# Controller_Sheet.net
KiCad netlist of a schematic drawn in Altium Designer
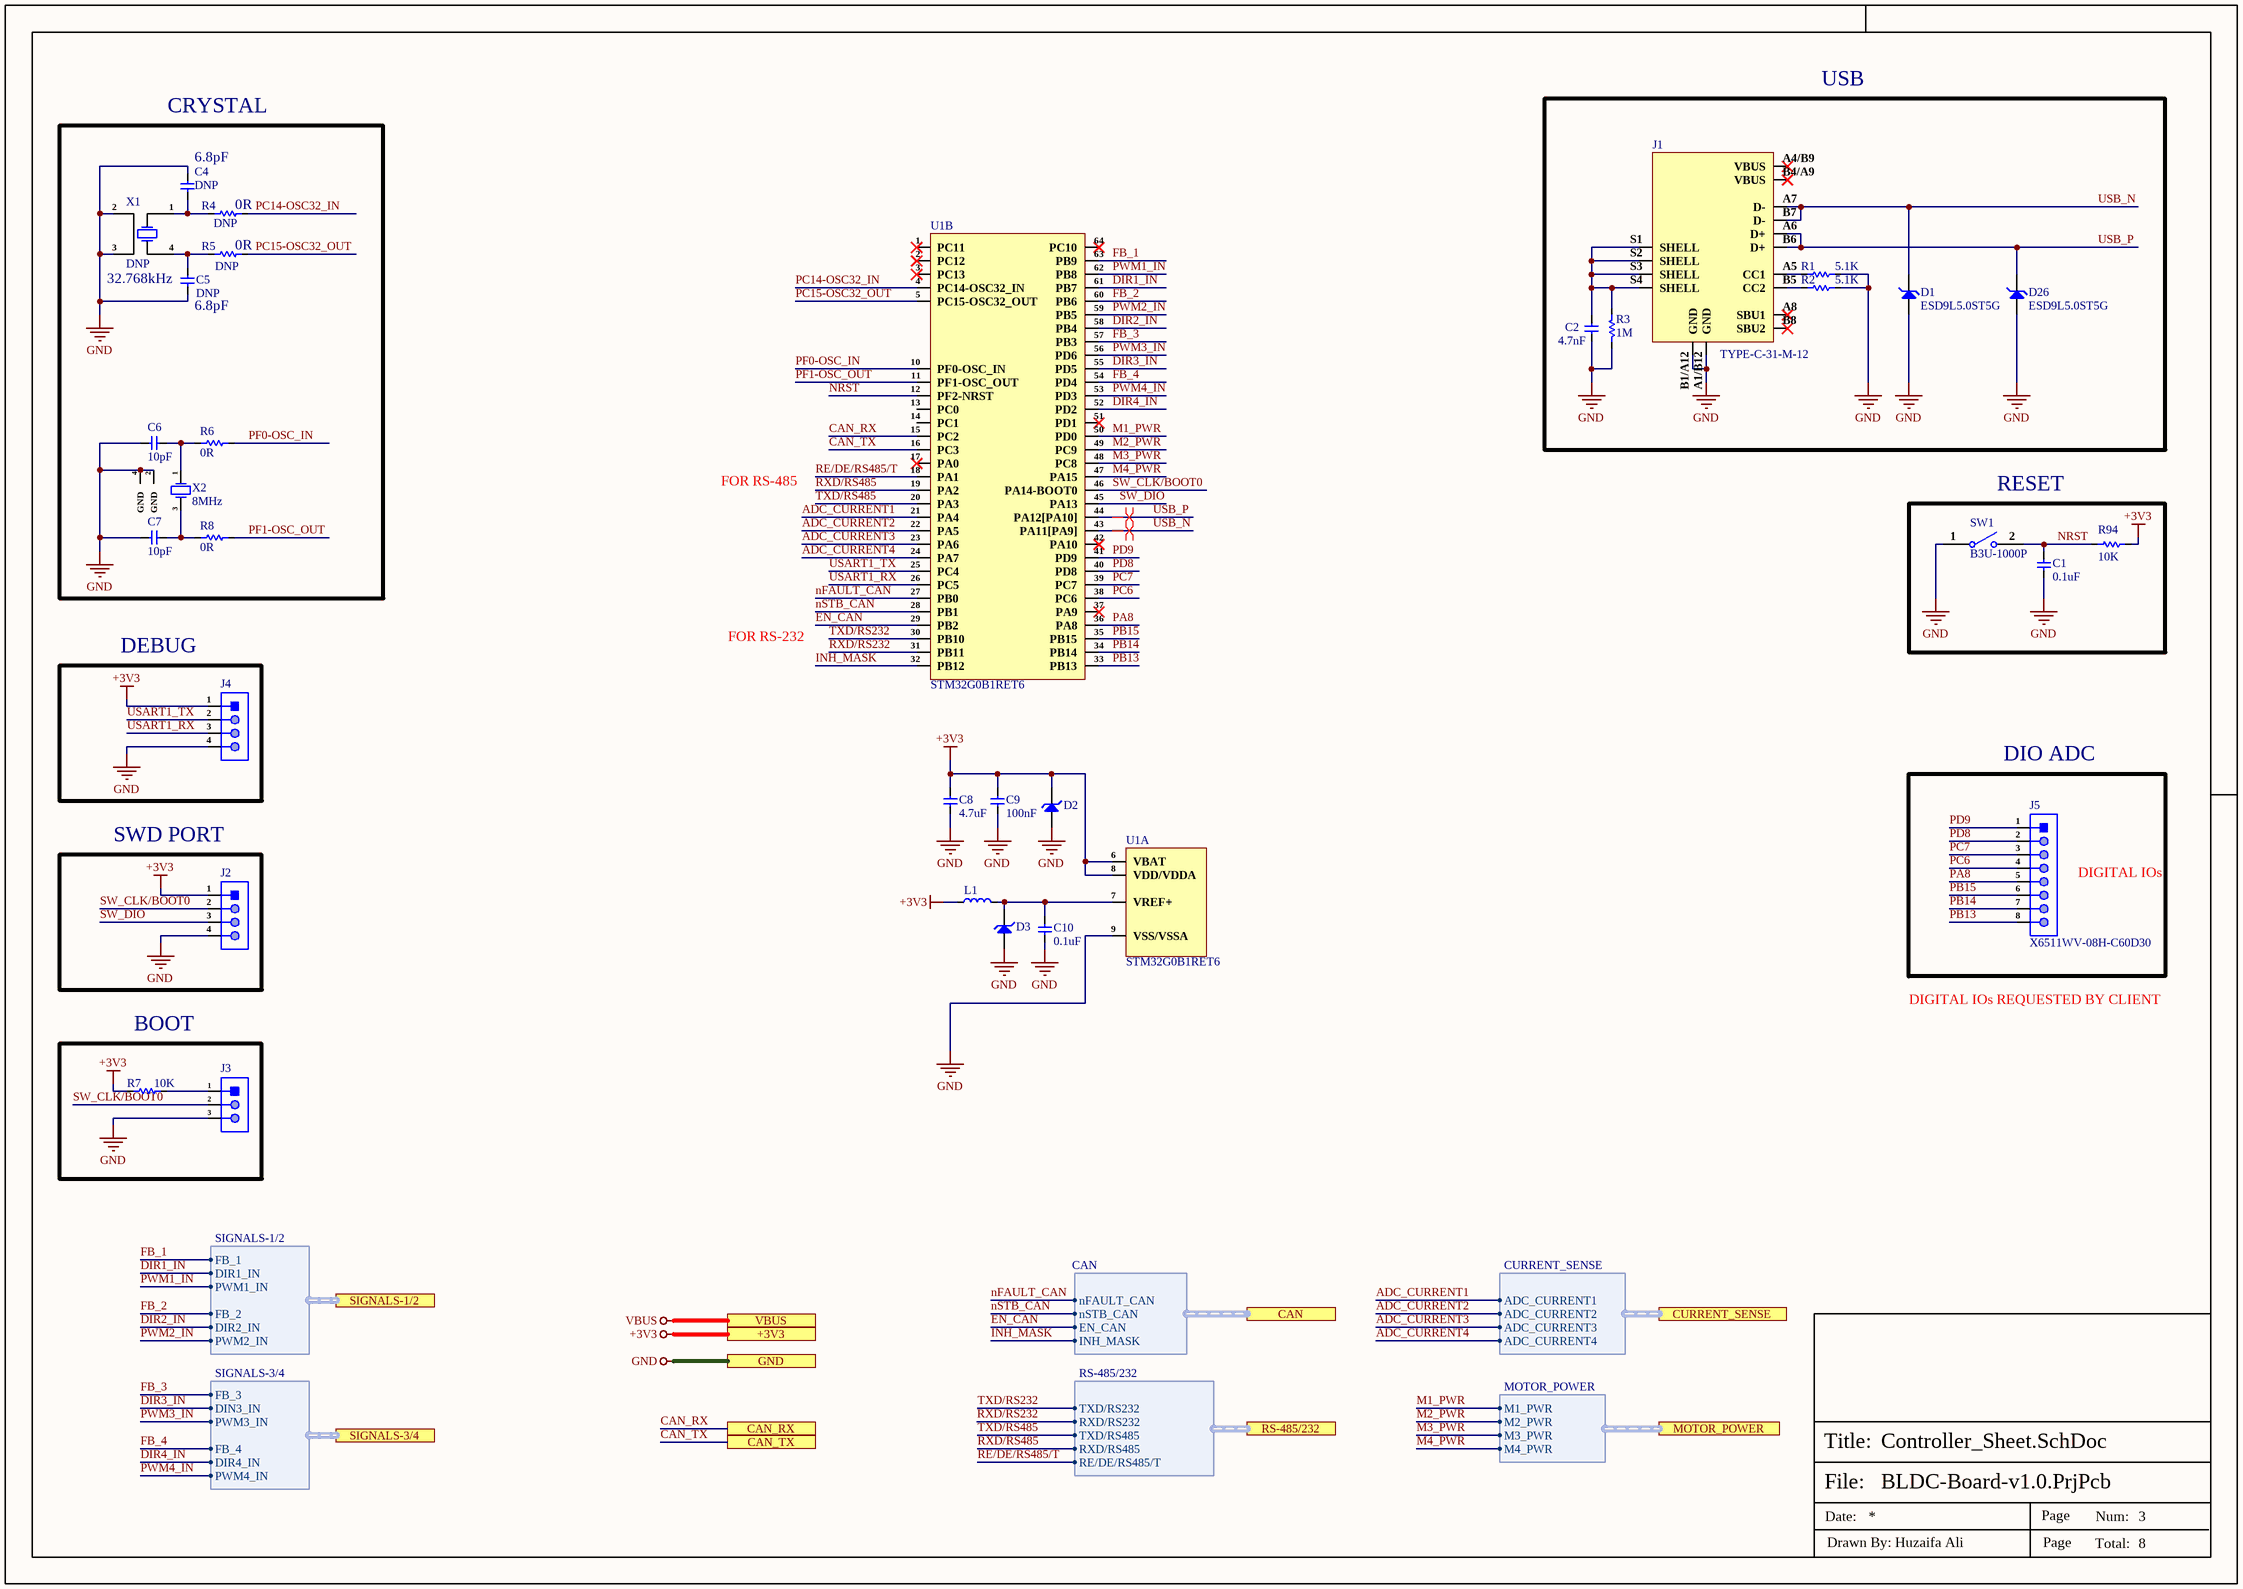
[diagram p0: Controller_Sheet.SchDoc]

(export (version "E")
  (design (tool "Eeschema 10.0.6"))
  (components
    (comp (ref "C1")
      (value "0.1uF")
      (footprint "Cap-0402")
      (description "CAP CER 0.1UF 16V X7R 0402")
      (fields
        (field (name "MANUFACTURER") "Yageo")
        (field (name "MANUFACTURER PART NUMBER") "CC0402JRX7R7BB104")
      )
      (libsource (lib "eSpark Libraries") (part "CC0402JRX7R7BB104"))
    )
    (comp (ref "C2")
      (value "4.7nF")
      (footprint "Cap-0603")
      (description "CAP CER 4700PF 50V C0G/NPO 0603")
      (fields
        (field (name "MANUFACTURER") "Yageo")
        (field (name "MANUFACTURER PART NUMBER") "CC0603JRNPO9BN472")
      )
      (libsource (lib "eSpark_centralized_Library(2022)") (part "CC0603JRNPO9BN472"))
    )
    (comp (ref "C4")
      (value "DNP")
      (footprint "Cap-0402")
      (description "CAP CER 6.8PF 50V C0G/NPO 0402")
      (fields
        (field (name "MANUFACTURER") "Yageo")
        (field (name "MANUFACTURER PART NUMBER") "CC0402CRNPO9BN6R8")
      )
      (libsource (lib "eSpark Libraries") (part "CC0402CRNPO9BN6R8"))
    )
    (comp (ref "C5")
      (value "DNP")
      (footprint "Cap-0402")
      (description "CAP CER 6.8PF 50V C0G/NPO 0402")
      (fields
        (field (name "MANUFACTURER") "Yageo")
        (field (name "MANUFACTURER PART NUMBER") "CC0402CRNPO9BN6R8")
      )
      (libsource (lib "eSpark Libraries") (part "CC0402CRNPO9BN6R8"))
    )
    (comp (ref "C6")
      (value "10pF")
      (footprint "Cap-0402")
      (description "CAP CER 10PF 50V C0G/NP0 0402")
      (fields
        (field (name "MANUFACTURER") "Murata")
        (field (name "MANUFACTURER PART NUMBER") "GRM1555C1H100JA01D")
      )
      (libsource (lib "eSpark Libraries") (part "GRM1555C1H100JA01D"))
    )
    (comp (ref "C7")
      (value "10pF")
      (footprint "Cap-0402")
      (description "CAP CER 10PF 50V C0G/NP0 0402")
      (fields
        (field (name "MANUFACTURER") "Murata")
        (field (name "MANUFACTURER PART NUMBER") "GRM1555C1H100JA01D")
      )
      (libsource (lib "eSpark Libraries") (part "GRM1555C1H100JA01D"))
    )
    (comp (ref "C8")
      (value "4.7uF")
      (footprint "Cap-0402")
      (description "CAP CER 4.7UF 10V X5R 0402")
      (fields
        (field (name "MANUFACTURER") "Yageo")
        (field (name "MANUFACTURER PART NUMBER") "CC0402KRX5R6BB475")
      )
      (libsource (lib "eSpark Libraries") (part "CC0402KRX5R6BB475"))
    )
    (comp (ref "C9")
      (value "100nF")
      (footprint "cap-0402")
      (description "CAP CER 0.1UF 50V X7R 0402")
      (fields
        (field (name "MANUFACTURER") "TDK")
        (field (name "MANUFACTURER PART NUMBER") "C1005X7R1H104KT000F")
      )
      (libsource (lib "eSpark Libraries") (part "C1005X7R1H104KT000F"))
    )
    (comp (ref "C10")
      (value "0.1uF")
      (footprint "Cap-0402")
      (description "CAP CER 0.1UF 16V X7R 0402")
      (fields
        (field (name "MANUFACTURER") "Yageo")
        (field (name "MANUFACTURER PART NUMBER") "CC0402JRX7R7BB104")
      )
      (libsource (lib "eSpark Libraries") (part "CC0402JRX7R7BB104"))
    )
    (comp (ref "D1")
      (value "ESD9L5.0ST5G")
      (footprint "SOD-923.")
      (description "TVS DIODE 5V 9.8V SOD923")
      (fields (field (name "MANUFACTURER") "ON Semiconductor") (field (name "LCSC PART NUMBER") "C82326"))
      (libsource (lib "eSpark Libraries") (part "ESD9L5.0ST5G"))
    )
    (comp (ref "D2")
      (value "AZ3003-01G")
      (footprint "SOD-123")
      (description "TVS SURGE PROTECTOR 1-CH 3.3V")
      (fields (field (name "MANUFACTURER") "Amazing"))
      (libsource (lib "eSpark Libraries") (part "AZ3003-01G"))
    )
    (comp (ref "D3")
      (value "AZ3003-01G")
      (footprint "SOD-123")
      (description "TVS SURGE PROTECTOR 1-CH 3.3V")
      (fields (field (name "MANUFACTURER") "Amazing"))
      (libsource (lib "eSpark Libraries") (part "AZ3003-01G"))
    )
    (comp (ref "D26")
      (value "ESD9L5.0ST5G")
      (footprint "SOD-923.")
      (description "TVS DIODE 5V 9.8V SOD923")
      (fields (field (name "MANUFACTURER") "ON Semiconductor") (field (name "LCSC PART NUMBER") "C82326"))
      (libsource (lib "eSpark Libraries") (part "ESD9L5.0ST5G"))
    )
    (comp (ref "J1")
      (value "TYPE-C-31-M-12")
      (footprint "TYPE-C-31-M-12_")
      (description "5A 1 16P Female Type-C SMD USB Connectors ROHS")
      (fields
        (field (name "MANUFACTURER") "Korean Hroparts Elec")
        (field (name "LCSC PART NUMBER") "C165948")
      )
      (libsource (lib "eSpark Libraries") (part "TYPE-C-31-M-12"))
    )
    (comp (ref "J2")
      (value "X6511WV-04H-C60D30")
      (footprint "HDR1X4_")
      (fields (field (name "MANUFACTURER") "XKB") (field (name "LCSC PART NUMBER") "C706876"))
      (libsource (lib "eSpark Libraries") (part "X6511WV-04H-C60D30"))
    )
    (comp (ref "J3")
      (value "68000-103HLF")
      (footprint "HDR1X3_")
      (description "CONN HEADER VERT 3POS 2.54MM")
      (fields (field (name "LCSC PART NUMBER") "C168677"))
      (libsource (lib "eSpark Libraries") (part "68000-103HLF"))
    )
    (comp (ref "J4")
      (value "X6511WV-04H-C60D30")
      (footprint "HDR1X4_")
      (fields (field (name "MANUFACTURER") "XKB") (field (name "LCSC PART NUMBER") "C706876"))
      (libsource (lib "eSpark Libraries") (part "X6511WV-04H-C60D30"))
    )
    (comp (ref "J5")
      (value "X6511WV-08H-C60D30")
      (footprint "HDR 1x8 TH male")
      (fields (field (name "MANUFACTURER") "XKB") (field (name "LCSC PART NUMBER") "C706880"))
      (libsource (lib "eSpark Libraries") (part "X6511WV-08H-C60D30"))
    )
    (comp (ref "L1")
      (value "BLM15AG601SN1D")
      (footprint "IND-0402")
      (description "FERRITE BEAD 600 OHM 0402 1LN")
      (fields (field (name "MANUFACTURER") "Murata") (field (name "TOLERANCE") "25%"))
      (libsource (lib "eSpark Libraries") (part "BLM15AG601SN1D"))
    )
    (comp (ref "R1")
      (value "5.1K")
      (footprint "Res-0402")
      (description "RES 5.1K OHM 1% 1/16W 0402")
      (fields
        (field (name "MANUFACTURER") "Yageo")
        (field (name "MANUFACTURER PART NUMBER") "RC0402FR-075K1L")
      )
      (libsource (lib "eSpark Libraries") (part "RC0402FR-075K1L"))
    )
    (comp (ref "R2")
      (value "5.1K")
      (footprint "Res-0402")
      (description "RES 5.1K OHM 1% 1/16W 0402")
      (fields
        (field (name "MANUFACTURER") "Yageo")
        (field (name "MANUFACTURER PART NUMBER") "RC0402FR-075K1L")
      )
      (libsource (lib "eSpark Libraries") (part "RC0402FR-075K1L"))
    )
    (comp (ref "R3")
      (value "1M")
      (footprint "Res-0402")
      (description "RES SMD 1M OHM 5% 1/16W 0402")
      (fields
        (field (name "MANUFACTURER") "Yageo")
        (field (name "MANUFACTURER PART NUMBER") "AF0402JR-071ML")
      )
      (libsource (lib "eSpark_centralized_Library(2022)") (part "AF0402JR-071ML"))
    )
    (comp (ref "R4")
      (value "DNP")
      (footprint "Res-0603")
      (description "RES 0 OHM JUMPER 1/10W 0603")
      (fields
        (field (name "MANUFACTURER") "Yageo")
        (field (name "MANUFACTURER PART NUMBER") "RC0603JR-070RL")
      )
      (libsource (lib "eSpark Libraries") (part "RC0603JR-070RL"))
    )
    (comp (ref "R5")
      (value "DNP")
      (footprint "Res-0603")
      (description "RES 0 OHM JUMPER 1/10W 0603")
      (fields
        (field (name "MANUFACTURER") "Yageo")
        (field (name "MANUFACTURER PART NUMBER") "RC0603JR-070RL")
      )
      (libsource (lib "eSpark Libraries") (part "RC0603JR-070RL"))
    )
    (comp (ref "R6")
      (value "0R")
      (footprint "Res-0603")
      (description "RES 0 OHM JUMPER 1/10W 0603")
      (fields
        (field (name "MANUFACTURER") "Yageo")
        (field (name "MANUFACTURER PART NUMBER") "RC0603JR-070RL")
      )
      (libsource (lib "eSpark Libraries") (part "RC0603JR-070RL"))
    )
    (comp (ref "R7")
      (value "10K")
      (footprint "Res-0402")
      (description "RES 10K OHM 1% 1/16W 0402")
      (fields
        (field (name "MANUFACTURER") "Yageo")
        (field (name "MANUFACTURER PART NUMBER") "RC0402FR-0710KL")
      )
      (libsource (lib "eSpark Libraries") (part "RC0402FR-0710KL"))
    )
    (comp (ref "R8")
      (value "0R")
      (footprint "Res-0603")
      (description "RES 0 OHM JUMPER 1/10W 0603")
      (fields
        (field (name "MANUFACTURER") "Yageo")
        (field (name "MANUFACTURER PART NUMBER") "RC0603JR-070RL")
      )
      (libsource (lib "eSpark Libraries") (part "RC0603JR-070RL"))
    )
    (comp (ref "R94")
      (value "10K")
      (footprint "Res-0402")
      (description "RES 10K OHM 1% 1/16W 0402")
      (fields
        (field (name "MANUFACTURER") "Yageo")
        (field (name "MANUFACTURER PART NUMBER") "RC0402FR-0710KL")
      )
      (libsource (lib "eSpark Libraries") (part "RC0402FR-0710KL"))
    )
    (comp (ref "SW1")
      (value "B3U-1000P")
      (footprint "B3U-1000P")
      (description "SWITCH TACTILE SPST-NO 0.05A 12V")
      (fields (field (name "MANUFACTURER") "Omron") (field (name "LCSC PART NUMBER") "C231329"))
      (libsource (lib "eSpark Libraries") (part "B3U-1000P"))
    )
    (comp (ref "U1")
      (value "STM32G0B1RET6")
      (footprint "LQFP-64(10x10)")
      (description "IC MCU 32BIT 512KB FLASH 64LQFP")
      (fields (field (name "MANUFACTURER") "STMicroelectronics") (field (name "LCSC PART NUMBER") "C2829307"))
      (libsource (lib "eSpark Libraries") (part "STM32G0B1RET6"))
    )
    (comp (ref "X1")
      (value "DNP")
      (footprint "MC-306")
      (description "32.768kHz 12.5pF ±20ppm MC-306 Crystals ROHS")
      (fields
        (field (name "MANUFACTURER") "Seiko Epson")
        (field (name "MANUFACTURER PART NUMBER") "MC-306 32.7680K-A0:ROHS")
      )
      (libsource (lib "eSpark Libraries") (part "MC-306 32.7680K-A0{colon}ROHS"))
    )
    (comp (ref "X2")
      (value "8MHz")
      (footprint "5TJ480000XYLBC_")
      (description "8MHz 18pF ±10ppm SMD5032-4P Crystals ROHS")
      (fields (field (name "MANUFACTURER") "JYJE") (field (name "MANUFACTURER PART NUMBER") "5TJ480000XYLBC"))
      (libsource (lib "eSpark Libraries") (part "5TJ480000XYLBC"))
    )
  )
  (nets
    (net (code "7") (name "+3V3") (class "Default")
      (node (ref "C8") (pin "2") (pinfunction "2_2") (pintype "passive"))
      (node (ref "C9") (pin "2") (pinfunction "2_2") (pintype "passive"))
      (node (ref "D2") (pin "2") (pinfunction "K_2") (pintype "passive"))
      (node (ref "J2") (pin "1") (pinfunction "1_1") (pintype "passive"))
      (node (ref "J4") (pin "1") (pinfunction "1_1") (pintype "passive"))
      (node (ref "L1") (pin "1") (pinfunction "1_1") (pintype "passive"))
      (node (ref "R7") (pin "2") (pinfunction "2_2") (pintype "passive"))
      (node (ref "R94") (pin "2") (pinfunction "2_2") (pintype "passive"))
      (node (ref "U1") (pin "6") (pinfunction "VBAT_6") (pintype "passive"))
      (node (ref "U1") (pin "8") (pinfunction "VDD/VDDA_8") (pintype "passive"))
    )
    (net (code "8") (name "/ADC_CURRENT1") (class "Default")
      (node (ref "U1") (pin "21") (pinfunction "PA4_21") (pintype "passive"))
    )
    (net (code "9") (name "/ADC_CURRENT2") (class "Default")
      (node (ref "U1") (pin "22") (pinfunction "PA5_22") (pintype "passive"))
    )
    (net (code "10") (name "/ADC_CURRENT3") (class "Default")
      (node (ref "U1") (pin "23") (pinfunction "PA6_23") (pintype "passive"))
    )
    (net (code "11") (name "/ADC_CURRENT4") (class "Default")
      (node (ref "U1") (pin "24") (pinfunction "PA7_24") (pintype "passive"))
    )
    (net (code "12") (name "/CAN_RX") (class "Default")
      (node (ref "U1") (pin "15") (pinfunction "PC2_15") (pintype "passive"))
    )
    (net (code "13") (name "/CAN_TX") (class "Default")
      (node (ref "U1") (pin "16") (pinfunction "PC3_16") (pintype "passive"))
    )
    (net (code "14") (name "/DIR1_IN") (class "Default")
      (node (ref "U1") (pin "61") (pinfunction "PB7_61") (pintype "passive"))
    )
    (net (code "15") (name "/DIR2_IN") (class "Default")
      (node (ref "U1") (pin "58") (pinfunction "PB4_58") (pintype "passive"))
    )
    (net (code "16") (name "/DIR3_IN") (class "Default")
      (node (ref "U1") (pin "55") (pinfunction "PD5_55") (pintype "passive"))
    )
    (net (code "17") (name "/DIR4_IN") (class "Default")
      (node (ref "U1") (pin "52") (pinfunction "PD2_52") (pintype "passive"))
    )
    (net (code "18") (name "/EN_CAN") (class "Default")
      (node (ref "U1") (pin "29") (pinfunction "PB2_29") (pintype "passive"))
    )
    (net (code "19") (name "/FB_1") (class "Default")
      (node (ref "U1") (pin "63") (pinfunction "PB9_63") (pintype "passive"))
    )
    (net (code "20") (name "/FB_2") (class "Default")
      (node (ref "U1") (pin "60") (pinfunction "PB6_60") (pintype "passive"))
    )
    (net (code "21") (name "/FB_3") (class "Default")
      (node (ref "U1") (pin "57") (pinfunction "PB3_57") (pintype "passive"))
    )
    (net (code "22") (name "/FB_4") (class "Default")
      (node (ref "U1") (pin "54") (pinfunction "PD4_54") (pintype "passive"))
    )
    (net (code "23") (name "/INH_MASK") (class "Default")
      (node (ref "U1") (pin "32") (pinfunction "PB12_32") (pintype "passive"))
    )
    (net (code "24") (name "/M1_PWR") (class "Default")
      (node (ref "U1") (pin "50") (pinfunction "PD0_50") (pintype "passive"))
    )
    (net (code "25") (name "/M2_PWR") (class "Default")
      (node (ref "U1") (pin "49") (pinfunction "PC9_49") (pintype "passive"))
    )
    (net (code "26") (name "/M3_PWR") (class "Default")
      (node (ref "U1") (pin "48") (pinfunction "PC8_48") (pintype "passive"))
    )
    (net (code "27") (name "/M4_PWR") (class "Default")
      (node (ref "U1") (pin "47") (pinfunction "PA15_47") (pintype "passive"))
    )
    (net (code "28") (name "/NRST") (class "Default")
      (node (ref "C1") (pin "2") (pinfunction "2_2") (pintype "passive"))
      (node (ref "R94") (pin "1") (pinfunction "1_1") (pintype "passive"))
      (node (ref "SW1") (pin "2") (pinfunction "2_2") (pintype "passive"))
      (node (ref "U1") (pin "12") (pinfunction "PF2-NRST_12") (pintype "passive"))
    )
    (net (code "29") (name "/PA8") (class "Default")
      (node (ref "J5") (pin "5") (pinfunction "5_5") (pintype "passive"))
      (node (ref "U1") (pin "36") (pinfunction "PA8_36") (pintype "passive"))
    )
    (net (code "30") (name "/PB13") (class "Default")
      (node (ref "J5") (pin "8") (pinfunction "8_8") (pintype "passive"))
      (node (ref "U1") (pin "33") (pinfunction "PB13_33") (pintype "passive"))
    )
    (net (code "31") (name "/PB14") (class "Default")
      (node (ref "J5") (pin "7") (pinfunction "7_7") (pintype "passive"))
      (node (ref "U1") (pin "34") (pinfunction "PB14_34") (pintype "passive"))
    )
    (net (code "32") (name "/PB15") (class "Default")
      (node (ref "J5") (pin "6") (pinfunction "6_6") (pintype "passive"))
      (node (ref "U1") (pin "35") (pinfunction "PB15_35") (pintype "passive"))
    )
    (net (code "33") (name "/PC6") (class "Default")
      (node (ref "J5") (pin "4") (pinfunction "4_4") (pintype "passive"))
      (node (ref "U1") (pin "38") (pinfunction "PC6_38") (pintype "passive"))
    )
    (net (code "34") (name "/PC7") (class "Default")
      (node (ref "J5") (pin "3") (pinfunction "3_3") (pintype "passive"))
      (node (ref "U1") (pin "39") (pinfunction "PC7_39") (pintype "passive"))
    )
    (net (code "35") (name "/PC14-OSC32_IN") (class "Default")
      (node (ref "R4") (pin "2") (pinfunction "2_2") (pintype "passive"))
      (node (ref "U1") (pin "4") (pinfunction "PC14-OSC32_IN_4") (pintype "passive"))
    )
    (net (code "36") (name "/PC15-OSC32_OUT") (class "Default")
      (node (ref "R5") (pin "2") (pinfunction "2_2") (pintype "passive"))
      (node (ref "U1") (pin "5") (pinfunction "PC15-OSC32_OUT_5") (pintype "passive"))
    )
    (net (code "37") (name "/PD8") (class "Default")
      (node (ref "J5") (pin "2") (pinfunction "2_2") (pintype "passive"))
      (node (ref "U1") (pin "40") (pinfunction "PD8_40") (pintype "passive"))
    )
    (net (code "38") (name "/PD9") (class "Default")
      (node (ref "J5") (pin "1") (pinfunction "1_1") (pintype "passive"))
      (node (ref "U1") (pin "41") (pinfunction "PD9_41") (pintype "passive"))
    )
    (net (code "39") (name "/PF0-OSC_IN") (class "Default")
      (node (ref "R6") (pin "2") (pinfunction "2_2") (pintype "passive"))
      (node (ref "U1") (pin "10") (pinfunction "PF0-OSC_IN_10") (pintype "passive"))
    )
    (net (code "40") (name "/PF1-OSC_OUT") (class "Default")
      (node (ref "R8") (pin "2") (pinfunction "2_2") (pintype "passive"))
      (node (ref "U1") (pin "11") (pinfunction "PF1-OSC_OUT_11") (pintype "passive"))
    )
    (net (code "41") (name "/PWM1_IN") (class "Default")
      (node (ref "U1") (pin "62") (pinfunction "PB8_62") (pintype "passive"))
    )
    (net (code "42") (name "/PWM2_IN") (class "Default")
      (node (ref "U1") (pin "59") (pinfunction "PB5_59") (pintype "passive"))
    )
    (net (code "43") (name "/PWM3_IN") (class "Default")
      (node (ref "U1") (pin "56") (pinfunction "PD6_56") (pintype "passive"))
    )
    (net (code "44") (name "/PWM4_IN") (class "Default")
      (node (ref "U1") (pin "53") (pinfunction "PD3_53") (pintype "passive"))
    )
    (net (code "45") (name "/RE{slash}DE{slash}RS485{slash}T") (class "Default")
      (node (ref "U1") (pin "18") (pinfunction "PA1_18") (pintype "passive"))
    )
    (net (code "46") (name "/RXD{slash}RS232") (class "Default")
      (node (ref "U1") (pin "31") (pinfunction "PB11_31") (pintype "passive"))
    )
    (net (code "47") (name "/RXD{slash}RS485") (class "Default")
      (node (ref "U1") (pin "19") (pinfunction "PA2_19") (pintype "passive"))
    )
    (net (code "48") (name "/SW_CLK{slash}BOOT0") (class "Default")
      (node (ref "J2") (pin "2") (pinfunction "2_2") (pintype "passive"))
      (node (ref "J3") (pin "2") (pinfunction "2_2") (pintype "passive"))
      (node (ref "U1") (pin "46") (pinfunction "PA14-BOOT0_46") (pintype "passive"))
    )
    (net (code "49") (name "/SW_DIO") (class "Default")
      (node (ref "J2") (pin "3") (pinfunction "3_3") (pintype "passive"))
      (node (ref "U1") (pin "45") (pinfunction "PA13_45") (pintype "passive"))
    )
    (net (code "50") (name "/TXD{slash}RS232") (class "Default")
      (node (ref "U1") (pin "30") (pinfunction "PB10_30") (pintype "passive"))
    )
    (net (code "51") (name "/TXD{slash}RS485") (class "Default")
      (node (ref "U1") (pin "20") (pinfunction "PA3_20") (pintype "passive"))
    )
    (net (code "52") (name "/USART1_RX") (class "Default")
      (node (ref "J4") (pin "3") (pinfunction "3_3") (pintype "passive"))
      (node (ref "U1") (pin "26") (pinfunction "PC5_26") (pintype "passive"))
    )
    (net (code "53") (name "/USART1_TX") (class "Default")
      (node (ref "J4") (pin "2") (pinfunction "2_2") (pintype "passive"))
      (node (ref "U1") (pin "25") (pinfunction "PC4_25") (pintype "passive"))
    )
    (net (code "54") (name "/USB_N") (class "Default")
      (node (ref "D1") (pin "1") (pinfunction "K_1") (pintype "passive"))
      (node (ref "J1") (pin "A7") (pinfunction "D-_A7") (pintype "passive"))
      (node (ref "J1") (pin "B7") (pinfunction "D-_B7") (pintype "passive"))
      (node (ref "U1") (pin "43") (pinfunction "PA11[PA9]_43") (pintype "passive"))
    )
    (net (code "55") (name "/USB_P") (class "Default")
      (node (ref "D26") (pin "1") (pinfunction "K_1") (pintype "passive"))
      (node (ref "J1") (pin "A6") (pinfunction "D+_A6") (pintype "passive"))
      (node (ref "J1") (pin "B6") (pinfunction "D+_B6") (pintype "passive"))
      (node (ref "U1") (pin "44") (pinfunction "PA12[PA10]_44") (pintype "passive"))
    )
    (net (code "56") (name "/nFAULT_CAN") (class "Default")
      (node (ref "U1") (pin "27") (pinfunction "PB0_27") (pintype "passive"))
    )
    (net (code "57") (name "/nSTB_CAN") (class "Default")
      (node (ref "U1") (pin "28") (pinfunction "PB1_28") (pintype "passive"))
    )
    (net (code "64") (name "GND") (class "Default")
      (node (ref "C1") (pin "1") (pinfunction "1_1") (pintype "passive"))
      (node (ref "C10") (pin "1") (pinfunction "1_1") (pintype "passive"))
      (node (ref "C2") (pin "1") (pinfunction "1_1") (pintype "passive"))
      (node (ref "C4") (pin "1") (pinfunction "1_1") (pintype "passive"))
      (node (ref "C5") (pin "2") (pinfunction "2_2") (pintype "passive"))
      (node (ref "C6") (pin "2") (pinfunction "2_2") (pintype "passive"))
      (node (ref "C7") (pin "2") (pinfunction "2_2") (pintype "passive"))
      (node (ref "C8") (pin "1") (pinfunction "1_1") (pintype "passive"))
      (node (ref "C9") (pin "1") (pinfunction "1_1") (pintype "passive"))
      (node (ref "D1") (pin "2") (pinfunction "A_2") (pintype "passive"))
      (node (ref "D2") (pin "1") (pinfunction "A_1") (pintype "passive"))
      (node (ref "D26") (pin "2") (pinfunction "A_2") (pintype "passive"))
      (node (ref "D3") (pin "1") (pinfunction "A_1") (pintype "passive"))
      (node (ref "J1") (pin "A1/B12") (pinfunction "GND_A1/B12") (pintype "power_in"))
      (node (ref "J1") (pin "B1/A12") (pinfunction "GND_B1/A12") (pintype "power_in"))
      (node (ref "J2") (pin "4") (pinfunction "4_4") (pintype "passive"))
      (node (ref "J3") (pin "3") (pinfunction "3_3") (pintype "passive"))
      (node (ref "J4") (pin "4") (pinfunction "4_4") (pintype "passive"))
      (node (ref "R1") (pin "2") (pinfunction "2_2") (pintype "passive"))
      (node (ref "R2") (pin "2") (pinfunction "2_2") (pintype "passive"))
      (node (ref "R3") (pin "2") (pinfunction "2_2") (pintype "passive"))
      (node (ref "SW1") (pin "1") (pinfunction "1_1") (pintype "passive"))
      (node (ref "U1") (pin "9") (pinfunction "VSS/VSSA_9") (pintype "passive"))
      (node (ref "X1") (pin "2") (pinfunction "2_2") (pintype "passive"))
      (node (ref "X1") (pin "3") (pinfunction "3_3") (pintype "passive"))
      (node (ref "X2") (pin "2") (pinfunction "GND_2") (pintype "passive"))
      (node (ref "X2") (pin "4") (pinfunction "GND_4") (pintype "passive"))
    )
    (net (code "65") (name "Net-(C2-Pad2)") (class "Default")
      (node (ref "C2") (pin "2") (pinfunction "2_2") (pintype "passive"))
      (node (ref "J1") (pin "S1") (pinfunction "SHELL_S1") (pintype "passive"))
      (node (ref "J1") (pin "S2") (pinfunction "SHELL_S2") (pintype "passive"))
      (node (ref "J1") (pin "S3") (pinfunction "SHELL_S3") (pintype "passive"))
      (node (ref "J1") (pin "S4") (pinfunction "SHELL_S4") (pintype "passive"))
      (node (ref "R3") (pin "1") (pinfunction "1_1") (pintype "passive"))
    )
    (net (code "66") (name "Net-(D3-K)") (class "Default")
      (node (ref "C10") (pin "2") (pinfunction "2_2") (pintype "passive"))
      (node (ref "D3") (pin "2") (pinfunction "K_2") (pintype "passive"))
      (node (ref "L1") (pin "2") (pinfunction "2_2") (pintype "passive"))
      (node (ref "U1") (pin "7") (pinfunction "VREF+_7") (pintype "passive"))
    )
    (net (code "67") (name "Net-(J1-CC1)") (class "Default")
      (node (ref "J1") (pin "A5") (pinfunction "CC1_A5") (pintype "passive"))
      (node (ref "R1") (pin "1") (pinfunction "1_1") (pintype "passive"))
    )
    (net (code "68") (name "Net-(J1-CC2)") (class "Default")
      (node (ref "J1") (pin "B5") (pinfunction "CC2_B5") (pintype "passive"))
      (node (ref "R2") (pin "1") (pinfunction "1_1") (pintype "passive"))
    )
    (net (code "69") (name "Net-(J3-Pad1)") (class "Default")
      (node (ref "J3") (pin "1") (pinfunction "1_1") (pintype "passive"))
      (node (ref "R7") (pin "1") (pinfunction "1_1") (pintype "passive"))
    )
    (net (code "70") (name "Net-(X1-OSC1)") (class "Default")
      (node (ref "C4") (pin "2") (pinfunction "2_2") (pintype "passive"))
      (node (ref "R4") (pin "1") (pinfunction "1_1") (pintype "passive"))
      (node (ref "X1") (pin "1") (pinfunction "OSC1_1") (pintype "passive"))
    )
    (net (code "71") (name "Net-(X1-OSC2)") (class "Default")
      (node (ref "C5") (pin "1") (pinfunction "1_1") (pintype "passive"))
      (node (ref "R5") (pin "1") (pinfunction "1_1") (pintype "passive"))
      (node (ref "X1") (pin "4") (pinfunction "OSC2_4") (pintype "passive"))
    )
    (net (code "72") (name "Net-(X2-OSC1)") (class "Default")
      (node (ref "C6") (pin "1") (pinfunction "1_1") (pintype "passive"))
      (node (ref "R6") (pin "1") (pinfunction "1_1") (pintype "passive"))
      (node (ref "X2") (pin "1") (pinfunction "OSC1_1") (pintype "passive"))
    )
    (net (code "73") (name "Net-(X2-OSC2)") (class "Default")
      (node (ref "C7") (pin "1") (pinfunction "1_1") (pintype "passive"))
      (node (ref "R8") (pin "1") (pinfunction "1_1") (pintype "passive"))
      (node (ref "X2") (pin "3") (pinfunction "OSC2_3") (pintype "passive"))
    )
    (net (code "75") (name "unconnected-(J1-SBU1-PadA8)") (class "Default")
      (node (ref "J1") (pin "A8") (pinfunction "SBU1_A8") (pintype "passive+no_connect"))
    )
    (net (code "76") (name "unconnected-(J1-SBU2-PadB8)") (class "Default")
      (node (ref "J1") (pin "B8") (pinfunction "SBU2_B8") (pintype "passive+no_connect"))
    )
    (net (code "77") (name "unconnected-(J1-VBUS-PadA4{slash}B9)") (class "Default")
      (node (ref "J1") (pin "A4/B9") (pinfunction "VBUS_A4/B9") (pintype "power_in+no_connect"))
    )
    (net (code "78") (name "unconnected-(J1-VBUS-PadB4{slash}A9)") (class "Default")
      (node (ref "J1") (pin "B4/A9") (pinfunction "VBUS_B4/A9") (pintype "power_in+no_connect"))
    )
    (net (code "79") (name "unconnected-(U1B-PA0-Pad17)") (class "Default")
      (node (ref "U1") (pin "17") (pinfunction "PA0_17") (pintype "passive+no_connect"))
    )
    (net (code "80") (name "unconnected-(U1B-PA9-Pad37)") (class "Default")
      (node (ref "U1") (pin "37") (pinfunction "PA9_37") (pintype "passive+no_connect"))
    )
    (net (code "81") (name "unconnected-(U1B-PA10-Pad42)") (class "Default")
      (node (ref "U1") (pin "42") (pinfunction "PA10_42") (pintype "passive+no_connect"))
    )
    (net (code "82") (name "unconnected-(U1B-PC0-Pad13)") (class "Default")
      (node (ref "U1") (pin "13") (pinfunction "PC0_13") (pintype "passive"))
    )
    (net (code "83") (name "unconnected-(U1B-PC1-Pad14)") (class "Default")
      (node (ref "U1") (pin "14") (pinfunction "PC1_14") (pintype "passive"))
    )
    (net (code "84") (name "unconnected-(U1B-PC10-Pad64)") (class "Default")
      (node (ref "U1") (pin "64") (pinfunction "PC10_64") (pintype "passive+no_connect"))
    )
    (net (code "85") (name "unconnected-(U1B-PC11-Pad1)") (class "Default")
      (node (ref "U1") (pin "1") (pinfunction "PC11_1") (pintype "passive+no_connect"))
    )
    (net (code "86") (name "unconnected-(U1B-PC12-Pad2)") (class "Default")
      (node (ref "U1") (pin "2") (pinfunction "PC12_2") (pintype "passive+no_connect"))
    )
    (net (code "87") (name "unconnected-(U1B-PC13-Pad3)") (class "Default")
      (node (ref "U1") (pin "3") (pinfunction "PC13_3") (pintype "passive+no_connect"))
    )
    (net (code "88") (name "unconnected-(U1B-PD1-Pad51)") (class "Default")
      (node (ref "U1") (pin "51") (pinfunction "PD1_51") (pintype "passive+no_connect"))
    )
  )
)
